# driver_board.net
KiCad netlist of a schematic drawn in EAGLE
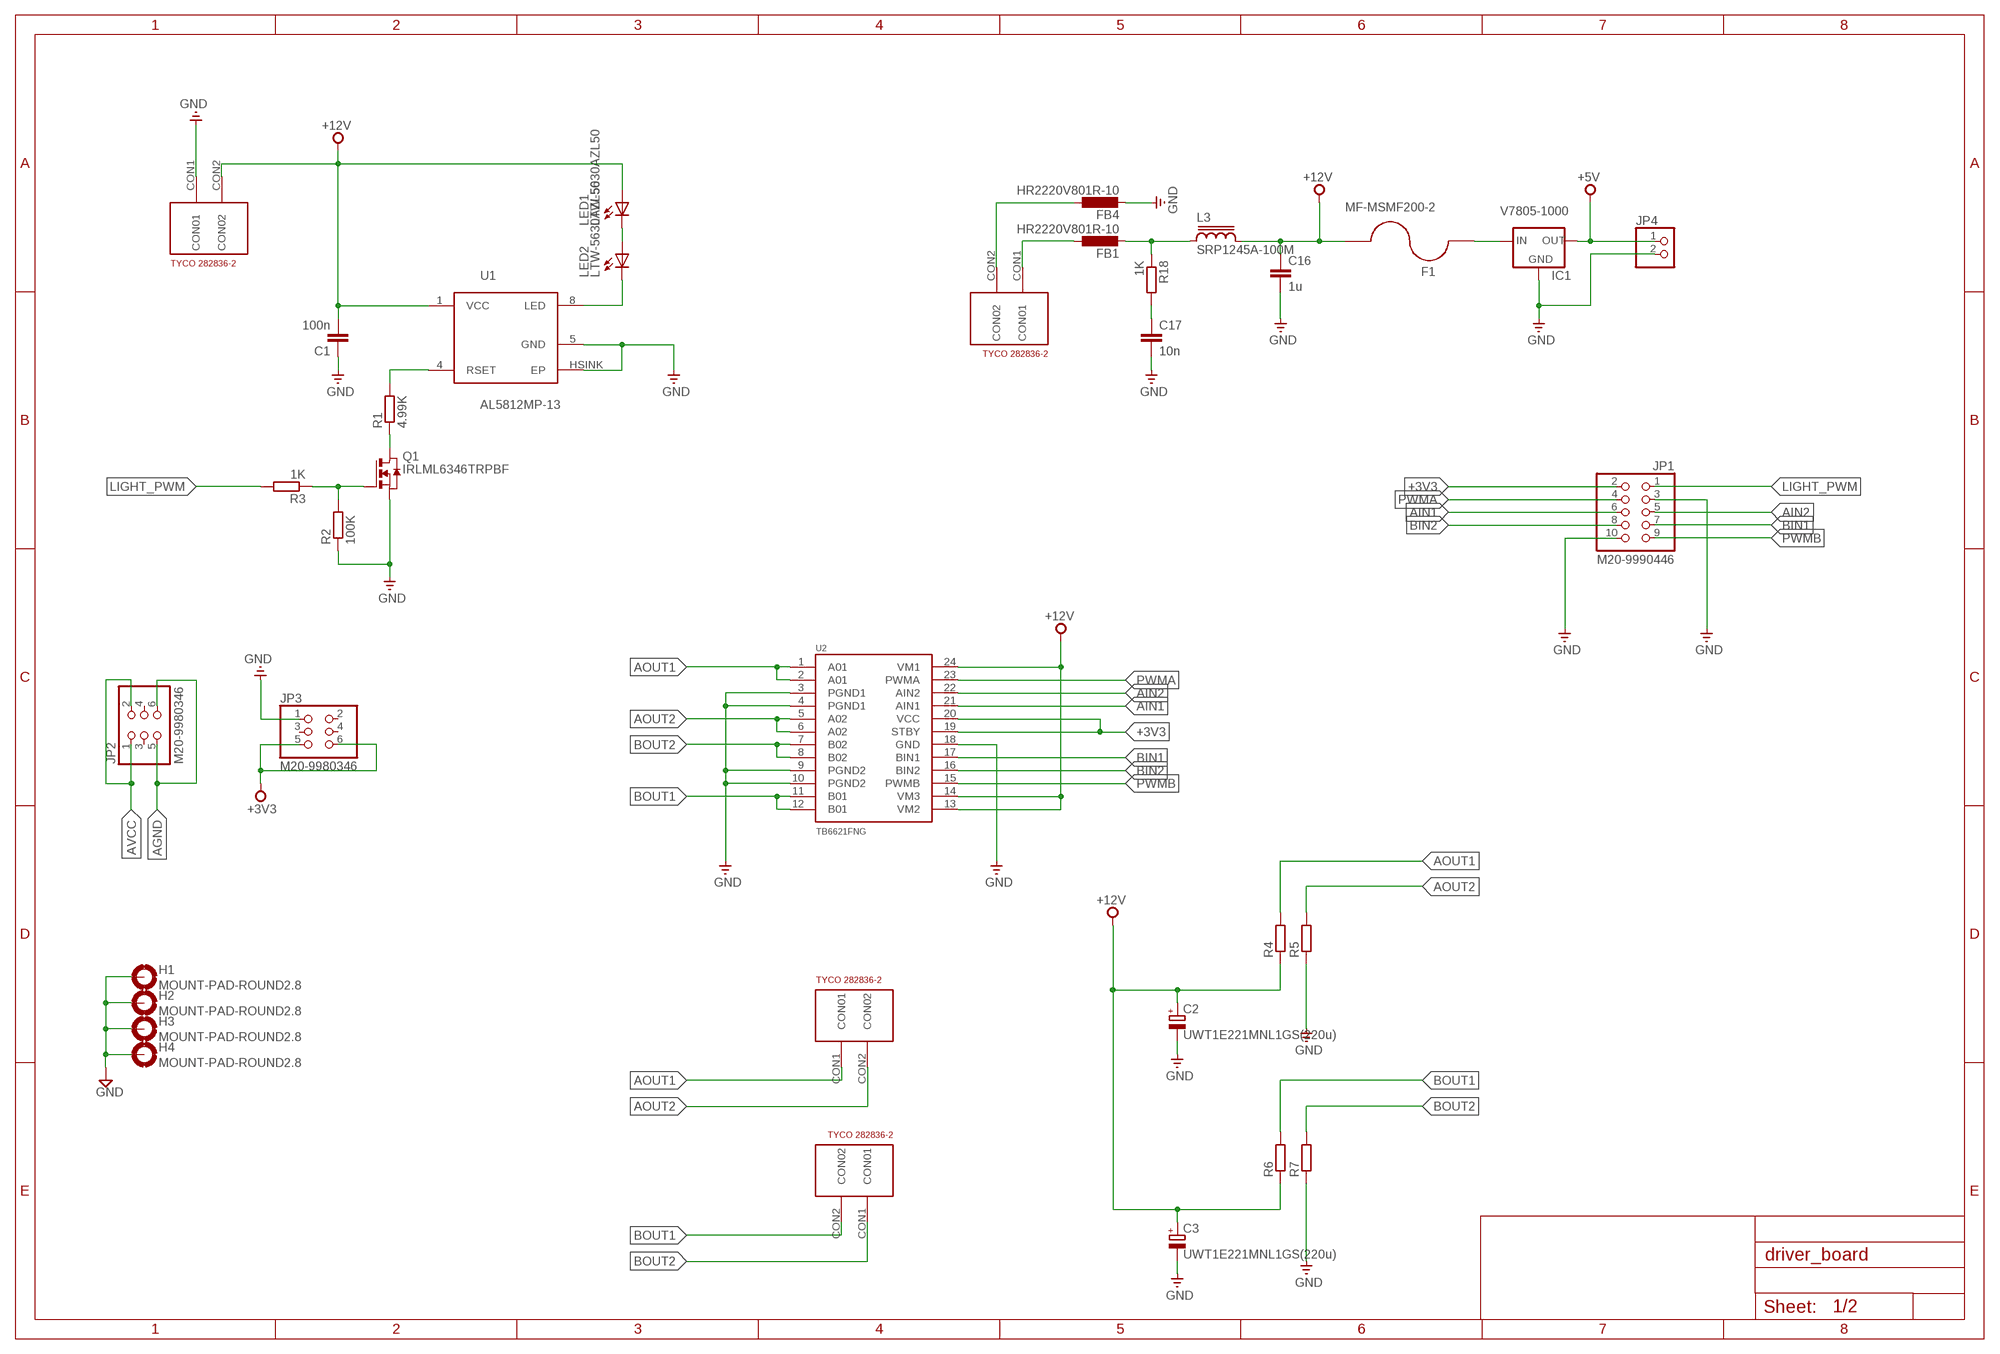
[diagram p0: schematic, sheet 1]
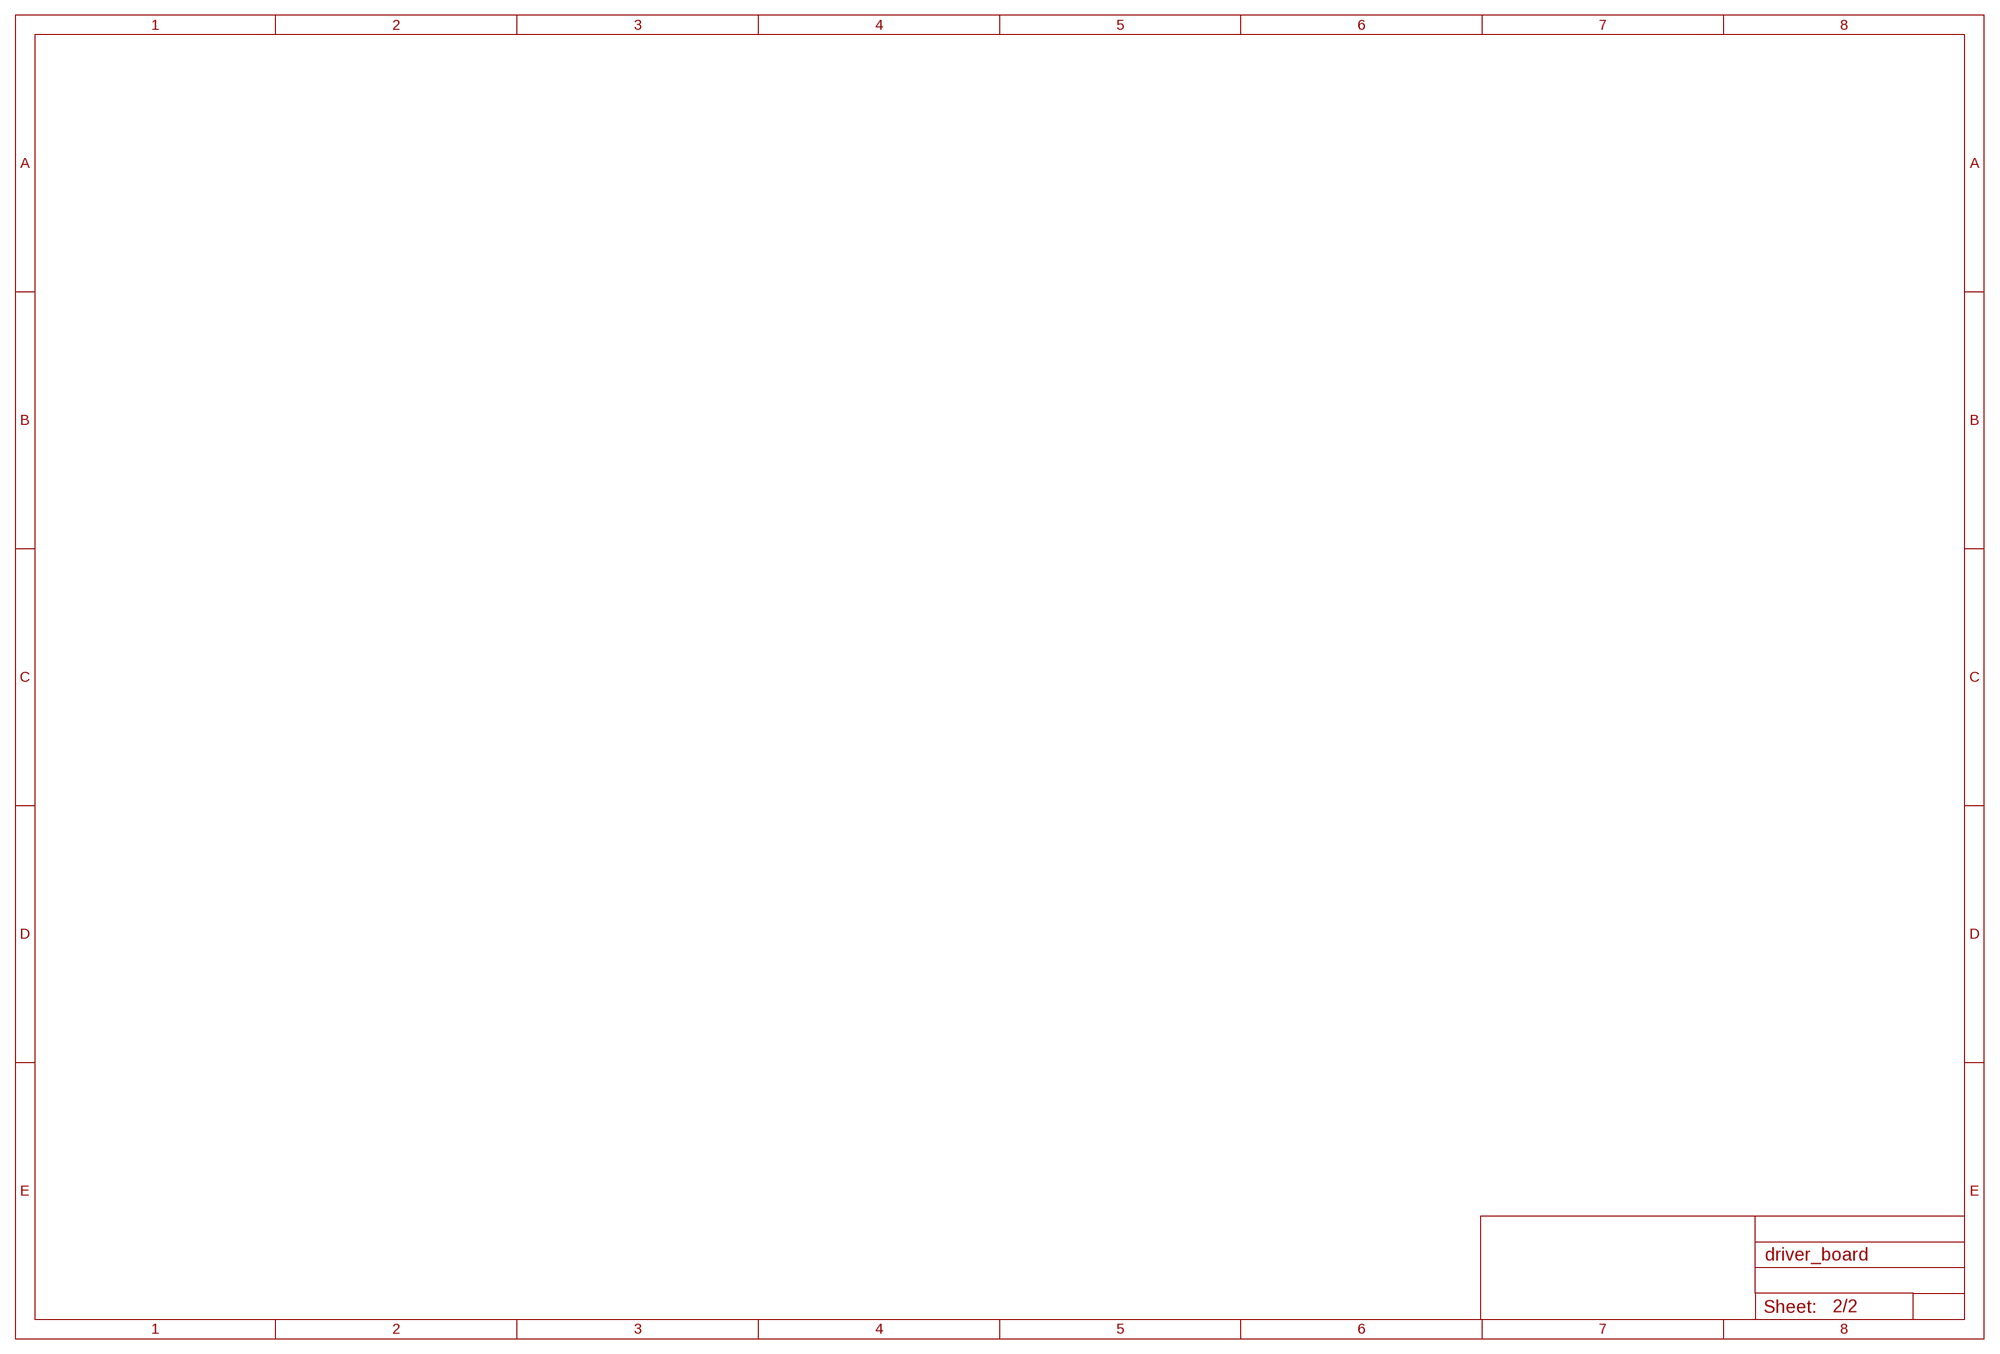
[diagram p1: schematic, sheet 2]

(export (version "E")
  (design (tool "Eeschema 10.0.6"))
  (components
    (comp (ref "C1")
      (value "100n")
      (footprint "eagle-import:C0402")
      (libsource (lib "eagle-import") (part "C-EUC0402"))
    )
    (comp (ref "C2")
      (value "UWT1E221MNL1GS(220u)")
      (footprint "eagle-import:153CLV-0810")
      (libsource (lib "eagle-import") (part "CPOL-EU153CLV-0810"))
    )
    (comp (ref "C3")
      (value "UWT1E221MNL1GS(220u)")
      (footprint "eagle-import:153CLV-0810")
      (libsource (lib "eagle-import") (part "CPOL-EU153CLV-0810"))
    )
    (comp (ref "C16")
      (value "1u")
      (footprint "eagle-import:C0402")
      (libsource (lib "eagle-import") (part "C-EUC0402"))
    )
    (comp (ref "C17")
      (value "10n")
      (footprint "eagle-import:C0402")
      (libsource (lib "eagle-import") (part "C-EUC0402"))
    )
    (comp (ref "F1")
      (value "MF-MSMF200-2")
      (footprint "eagle-import:1812")
      (fields (field (name "MANUFACTURER") "Bourns Inc.") (field (name "PART_NUMBER") "MF-MSMF075/24-2"))
      (libsource (lib "eagle-import") (part "MF-MSMF?075/24"))
    )
    (comp (ref "FB1")
      (value "HR2220V801R-10")
      (footprint "eagle-import:L5650M")
      (libsource (lib "eagle-import") (part "L-EUL5650M"))
    )
    (comp (ref "FB4")
      (value "HR2220V801R-10")
      (footprint "eagle-import:L5650M")
      (libsource (lib "eagle-import") (part "L-EUL5650M"))
    )
    (comp (ref "H1")
      (value "MOUNT-PAD-ROUND2.8")
      (footprint "eagle-import:2,8-PAD")
      (libsource (lib "eagle-import") (part "MOUNT-PAD-ROUND2.8"))
    )
    (comp (ref "H2")
      (value "MOUNT-PAD-ROUND2.8")
      (footprint "eagle-import:2,8-PAD")
      (libsource (lib "eagle-import") (part "MOUNT-PAD-ROUND2.8"))
    )
    (comp (ref "H3")
      (value "MOUNT-PAD-ROUND2.8")
      (footprint "eagle-import:2,8-PAD")
      (libsource (lib "eagle-import") (part "MOUNT-PAD-ROUND2.8"))
    )
    (comp (ref "H4")
      (value "MOUNT-PAD-ROUND2.8")
      (footprint "eagle-import:2,8-PAD")
      (libsource (lib "eagle-import") (part "MOUNT-PAD-ROUND2.8"))
    )
    (comp (ref "IC1")
      (value "V7805-1000")
      (footprint "eagle-import:DIP_3PIN")
      (libsource (lib "eagle-import") (part "VR_1OUTXX"))
    )
    (comp (ref "JP1")
      (value "M20-9990446")
      (footprint "eagle-import:2X05")
      (libsource (lib "eagle-import") (part "PINHD-2X5"))
    )
    (comp (ref "JP2")
      (value "M20-9980346")
      (footprint "eagle-import:2X03_SMT")
      (libsource (lib "eagle-import") (part "PINHD-2X3SMT"))
    )
    (comp (ref "JP3")
      (value "M20-9980346")
      (footprint "eagle-import:2X03_SMT")
      (libsource (lib "eagle-import") (part "PINHD-2X3SMT"))
    )
    (comp (ref "JP4")
      (value "PINHD-1X2")
      (footprint "eagle-import:1X02")
      (libsource (lib "eagle-import") (part "PINHD-1X2"))
    )
    (comp (ref "L3")
      (value "SRP1245A-100M")
      (footprint "eagle-import:SRP1250A")
      (libsource (lib "eagle-import") (part "SRP1250A"))
    )
    (comp (ref "LED1")
      (value "LTW-5630AZL50")
      (footprint "eagle-import:LITEON-5630")
      (libsource (lib "eagle-import") (part "LTW-5630AZL"))
    )
    (comp (ref "LED2")
      (value "LTW-5630AZL50")
      (footprint "eagle-import:LITEON-5630")
      (libsource (lib "eagle-import") (part "LTW-5630AZL"))
    )
    (comp (ref "Q1")
      (value "IRLML6346TRPBF")
      (footprint "eagle-import:SOT23")
      (libsource (lib "eagle-import") (part "NMOS-FETSOT23"))
    )
    (comp (ref "R1")
      (value "4.99K")
      (footprint "eagle-import:R0402")
      (libsource (lib "eagle-import") (part "R-EU_R0402"))
    )
    (comp (ref "R2")
      (value "100K")
      (footprint "eagle-import:R0402")
      (libsource (lib "eagle-import") (part "R-EU_R0402"))
    )
    (comp (ref "R3")
      (value "1K")
      (footprint "eagle-import:R0402")
      (libsource (lib "eagle-import") (part "R-EU_R0402"))
    )
    (comp (ref "R4")
      (value "R-EU_R0805")
      (footprint "eagle-import:R0805")
      (libsource (lib "eagle-import") (part "R-EU_R0805"))
    )
    (comp (ref "R5")
      (value "R-EU_R0805")
      (footprint "eagle-import:R0805")
      (libsource (lib "eagle-import") (part "R-EU_R0805"))
    )
    (comp (ref "R6")
      (value "R-EU_R0805")
      (footprint "eagle-import:R0805")
      (libsource (lib "eagle-import") (part "R-EU_R0805"))
    )
    (comp (ref "R7")
      (value "R-EU_R0805")
      (footprint "eagle-import:R0805")
      (libsource (lib "eagle-import") (part "R-EU_R0805"))
    )
    (comp (ref "R18")
      (value "1K")
      (footprint "eagle-import:R0402")
      (libsource (lib "eagle-import") (part "R-EU_R0402"))
    )
    (comp (ref "U$2")
      (value "282836-2")
      (footprint "eagle-import:282836-2")
      (libsource (lib "eagle-import") (part "282836-2"))
    )
    (comp (ref "U$4")
      (value "282836-2")
      (footprint "eagle-import:282836-2")
      (libsource (lib "eagle-import") (part "282836-2"))
    )
    (comp (ref "U$7")
      (value "282836-2")
      (footprint "eagle-import:282836-2")
      (libsource (lib "eagle-import") (part "282836-2"))
    )
    (comp (ref "U$8")
      (value "282836-2")
      (footprint "eagle-import:282836-2")
      (libsource (lib "eagle-import") (part "282836-2"))
    )
    (comp (ref "U1")
      (value "AL5812MP-13")
      (footprint "eagle-import:MSOP-8EP")
      (libsource (lib "eagle-import") (part "AL5812MP-13"))
    )
    (comp (ref "U2")
      (value "TB6621FNG")
      (footprint "eagle-import:SSOP24")
      (libsource (lib "eagle-import") (part "TB6621FNG"))
    )
  )
  (nets
    (net (code "1") (name "+3V3") (class "Default")
      (node (ref "JP1") (pin "2") (pinfunction "2_2") (pintype "passive"))
      (node (ref "JP3") (pin "5") (pinfunction "5_5") (pintype "passive"))
      (node (ref "JP3") (pin "6") (pinfunction "6_6") (pintype "passive"))
      (node (ref "U2") (pin "19") (pinfunction "STBY_19") (pintype "bidirectional"))
      (node (ref "U2") (pin "20") (pinfunction "VCC_20") (pintype "bidirectional"))
    )
    (net (code "2") (name "+5V") (class "Default")
      (node (ref "IC1") (pin "OUT") (pinfunction "OUT_OUT") (pintype "passive"))
      (node (ref "JP4") (pin "1") (pinfunction "1_1") (pintype "passive"))
    )
    (net (code "3") (name "+12V") (class "Default")
      (node (ref "C1") (pin "2") (pinfunction "2_2") (pintype "passive"))
      (node (ref "C16") (pin "1") (pinfunction "1_1") (pintype "passive"))
      (node (ref "C2") (pin "+") (pinfunction "+_+") (pintype "passive"))
      (node (ref "C3") (pin "+") (pinfunction "+_+") (pintype "passive"))
      (node (ref "F1") (pin "1") (pinfunction "1_1") (pintype "passive"))
      (node (ref "L3") (pin "2") (pinfunction "2_2") (pintype "passive"))
      (node (ref "LED1") (pin "A1") (pinfunction "A_A1") (pintype "passive"))
      (node (ref "LED1") (pin "A2") (pinfunction "A_A2") (pintype "passive"))
      (node (ref "LED1") (pin "A3") (pinfunction "A_A3") (pintype "passive"))
      (node (ref "R4") (pin "1") (pinfunction "1_1") (pintype "passive"))
      (node (ref "R6") (pin "1") (pinfunction "1_1") (pintype "passive"))
      (node (ref "U$4") (pin "CON2") (pinfunction "CON02_CON2") (pintype "bidirectional"))
      (node (ref "U1") (pin "1") (pinfunction "VCC_1") (pintype "bidirectional"))
      (node (ref "U2") (pin "13") (pinfunction "VM2_13") (pintype "bidirectional"))
      (node (ref "U2") (pin "14") (pinfunction "VM3_14") (pintype "bidirectional"))
      (node (ref "U2") (pin "24") (pinfunction "VM1_24") (pintype "bidirectional"))
    )
    (net (code "4") (name "AGND") (class "Default")
      (node (ref "FB4") (pin "1") (pinfunction "1_1") (pintype "passive"))
      (node (ref "JP2") (pin "5") (pinfunction "5_5") (pintype "passive"))
      (node (ref "JP2") (pin "6") (pinfunction "6_6") (pintype "passive"))
      (node (ref "U$2") (pin "CON2") (pinfunction "CON02_CON2") (pintype "bidirectional"))
    )
    (net (code "5") (name "AIN1") (class "Default")
      (node (ref "JP1") (pin "6") (pinfunction "6_6") (pintype "passive"))
      (node (ref "U2") (pin "21") (pinfunction "AIN1_21") (pintype "bidirectional"))
    )
    (net (code "6") (name "AIN2") (class "Default")
      (node (ref "JP1") (pin "5") (pinfunction "5_5") (pintype "passive"))
      (node (ref "U2") (pin "22") (pinfunction "AIN2_22") (pintype "bidirectional"))
    )
    (net (code "7") (name "AOUT1") (class "Default")
      (node (ref "R4") (pin "2") (pinfunction "2_2") (pintype "passive"))
      (node (ref "U$8") (pin "CON1") (pinfunction "CON01_CON1") (pintype "bidirectional"))
      (node (ref "U2") (pin "1") (pinfunction "A01_1") (pintype "bidirectional"))
      (node (ref "U2") (pin "2") (pinfunction "A01_2") (pintype "bidirectional"))
    )
    (net (code "8") (name "AOUT2") (class "Default")
      (node (ref "R5") (pin "2") (pinfunction "2_2") (pintype "passive"))
      (node (ref "U$8") (pin "CON2") (pinfunction "CON02_CON2") (pintype "bidirectional"))
      (node (ref "U2") (pin "5") (pinfunction "A02_5") (pintype "bidirectional"))
      (node (ref "U2") (pin "6") (pinfunction "A02_6") (pintype "bidirectional"))
    )
    (net (code "9") (name "AVCC") (class "Default")
      (node (ref "FB1") (pin "1") (pinfunction "1_1") (pintype "passive"))
      (node (ref "JP2") (pin "1") (pinfunction "1_1") (pintype "passive"))
      (node (ref "JP2") (pin "2") (pinfunction "2_2") (pintype "passive"))
      (node (ref "U$2") (pin "CON1") (pinfunction "CON01_CON1") (pintype "bidirectional"))
    )
    (net (code "10") (name "BIN1") (class "Default")
      (node (ref "JP1") (pin "7") (pinfunction "7_7") (pintype "passive"))
      (node (ref "U2") (pin "17") (pinfunction "BIN1_17") (pintype "bidirectional"))
    )
    (net (code "11") (name "BIN2") (class "Default")
      (node (ref "JP1") (pin "8") (pinfunction "8_8") (pintype "passive"))
      (node (ref "U2") (pin "16") (pinfunction "BIN2_16") (pintype "bidirectional"))
    )
    (net (code "12") (name "BOUT1") (class "Default")
      (node (ref "R6") (pin "2") (pinfunction "2_2") (pintype "passive"))
      (node (ref "U$7") (pin "CON2") (pinfunction "CON02_CON2") (pintype "bidirectional"))
      (node (ref "U2") (pin "11") (pinfunction "B01_11") (pintype "bidirectional"))
      (node (ref "U2") (pin "12") (pinfunction "B01_12") (pintype "bidirectional"))
    )
    (net (code "13") (name "BOUT2") (class "Default")
      (node (ref "R7") (pin "2") (pinfunction "2_2") (pintype "passive"))
      (node (ref "U$7") (pin "CON1") (pinfunction "CON01_CON1") (pintype "bidirectional"))
      (node (ref "U2") (pin "7") (pinfunction "B02_7") (pintype "bidirectional"))
      (node (ref "U2") (pin "8") (pinfunction "B02_8") (pintype "bidirectional"))
    )
    (net (code "14") (name "GND") (class "Default")
      (node (ref "C1") (pin "1") (pinfunction "1_1") (pintype "passive"))
      (node (ref "C16") (pin "2") (pinfunction "2_2") (pintype "passive"))
      (node (ref "C17") (pin "2") (pinfunction "2_2") (pintype "passive"))
      (node (ref "C2") (pin "-") (pinfunction "-_-") (pintype "passive"))
      (node (ref "C3") (pin "-") (pinfunction "-_-") (pintype "passive"))
      (node (ref "FB4") (pin "2") (pinfunction "2_2") (pintype "passive"))
      (node (ref "H1") (pin "B2,8") (pinfunction "MOUNT_B2,8") (pintype "passive"))
      (node (ref "H2") (pin "B2,8") (pinfunction "MOUNT_B2,8") (pintype "passive"))
      (node (ref "H3") (pin "B2,8") (pinfunction "MOUNT_B2,8") (pintype "passive"))
      (node (ref "H4") (pin "B2,8") (pinfunction "MOUNT_B2,8") (pintype "passive"))
      (node (ref "IC1") (pin "GND") (pinfunction "GND_GND") (pintype "input"))
      (node (ref "JP1") (pin "10") (pinfunction "10_10") (pintype "passive"))
      (node (ref "JP1") (pin "3") (pinfunction "3_3") (pintype "passive"))
      (node (ref "JP3") (pin "1") (pinfunction "1_1") (pintype "passive"))
      (node (ref "JP4") (pin "2") (pinfunction "2_2") (pintype "passive"))
      (node (ref "Q1") (pin "2") (pinfunction "S_2") (pintype "passive"))
      (node (ref "R2") (pin "1") (pinfunction "1_1") (pintype "passive"))
      (node (ref "R5") (pin "1") (pinfunction "1_1") (pintype "passive"))
      (node (ref "R7") (pin "1") (pinfunction "1_1") (pintype "passive"))
      (node (ref "U$4") (pin "CON1") (pinfunction "CON01_CON1") (pintype "bidirectional"))
      (node (ref "U1") (pin "5") (pinfunction "GND_5") (pintype "bidirectional"))
      (node (ref "U1") (pin "HSINK") (pinfunction "EP_HSINK") (pintype "bidirectional"))
      (node (ref "U2") (pin "10") (pinfunction "PGND2_10") (pintype "bidirectional"))
      (node (ref "U2") (pin "18") (pinfunction "GND_18") (pintype "bidirectional"))
      (node (ref "U2") (pin "3") (pinfunction "PGND1_3") (pintype "bidirectional"))
      (node (ref "U2") (pin "4") (pinfunction "PGND1_4") (pintype "bidirectional"))
      (node (ref "U2") (pin "9") (pinfunction "PGND2_9") (pintype "bidirectional"))
    )
    (net (code "15") (name "LIGHT_PWM") (class "Default")
      (node (ref "JP1") (pin "1") (pinfunction "1_1") (pintype "passive"))
      (node (ref "R3") (pin "2") (pinfunction "2_2") (pintype "passive"))
    )
    (net (code "16") (name "Net-(C17-Pad1)") (class "Default")
      (node (ref "C17") (pin "1") (pinfunction "1_1") (pintype "passive"))
      (node (ref "R18") (pin "2") (pinfunction "2_2") (pintype "passive"))
    )
    (net (code "17") (name "Net-(F1-Pad2)") (class "Default")
      (node (ref "F1") (pin "2") (pinfunction "2_2") (pintype "passive"))
      (node (ref "IC1") (pin "IN") (pinfunction "IN_IN") (pintype "input"))
    )
    (net (code "18") (name "Net-(FB1-Pad2)") (class "Default")
      (node (ref "FB1") (pin "2") (pinfunction "2_2") (pintype "passive"))
      (node (ref "L3") (pin "1") (pinfunction "1_1") (pintype "passive"))
      (node (ref "R18") (pin "1") (pinfunction "1_1") (pintype "passive"))
    )
    (net (code "19") (name "Net-(LED1-C-PadC1)") (class "Default")
      (node (ref "LED1") (pin "C1") (pinfunction "C_C1") (pintype "passive"))
      (node (ref "LED1") (pin "C2") (pinfunction "C_C2") (pintype "passive"))
      (node (ref "LED2") (pin "A1") (pinfunction "A_A1") (pintype "passive"))
      (node (ref "LED2") (pin "A2") (pinfunction "A_A2") (pintype "passive"))
      (node (ref "LED2") (pin "A3") (pinfunction "A_A3") (pintype "passive"))
    )
    (net (code "20") (name "Net-(Q1-D)") (class "Default")
      (node (ref "Q1") (pin "3") (pinfunction "D_3") (pintype "passive"))
      (node (ref "R1") (pin "1") (pinfunction "1_1") (pintype "passive"))
    )
    (net (code "21") (name "Net-(Q1-G)") (class "Default")
      (node (ref "Q1") (pin "1") (pinfunction "G_1") (pintype "passive"))
      (node (ref "R2") (pin "2") (pinfunction "2_2") (pintype "passive"))
      (node (ref "R3") (pin "1") (pinfunction "1_1") (pintype "passive"))
    )
    (net (code "22") (name "Net-(U1-LED)") (class "Default")
      (node (ref "LED2") (pin "C1") (pinfunction "C_C1") (pintype "passive"))
      (node (ref "LED2") (pin "C2") (pinfunction "C_C2") (pintype "passive"))
      (node (ref "U1") (pin "8") (pinfunction "LED_8") (pintype "bidirectional"))
    )
    (net (code "23") (name "Net-(U1-RSET)") (class "Default")
      (node (ref "R1") (pin "2") (pinfunction "2_2") (pintype "passive"))
      (node (ref "U1") (pin "4") (pinfunction "RSET_4") (pintype "bidirectional"))
    )
    (net (code "24") (name "PWMA") (class "Default")
      (node (ref "JP1") (pin "4") (pinfunction "4_4") (pintype "passive"))
      (node (ref "U2") (pin "23") (pinfunction "PWMA_23") (pintype "bidirectional"))
    )
    (net (code "25") (name "PWMB") (class "Default")
      (node (ref "JP1") (pin "9") (pinfunction "9_9") (pintype "passive"))
      (node (ref "U2") (pin "15") (pinfunction "PWMB_15") (pintype "bidirectional"))
    )
    (net (code "26") (name "unconnected-(JP2-Pad3)") (class "Default")
      (node (ref "JP2") (pin "3") (pinfunction "3_3") (pintype "passive"))
    )
    (net (code "27") (name "unconnected-(JP2-Pad4)") (class "Default")
      (node (ref "JP2") (pin "4") (pinfunction "4_4") (pintype "passive"))
    )
    (net (code "28") (name "unconnected-(JP3-Pad2)") (class "Default")
      (node (ref "JP3") (pin "2") (pinfunction "2_2") (pintype "passive"))
    )
    (net (code "29") (name "unconnected-(JP3-Pad3)") (class "Default")
      (node (ref "JP3") (pin "3") (pinfunction "3_3") (pintype "passive"))
    )
    (net (code "30") (name "unconnected-(JP3-Pad4)") (class "Default")
      (node (ref "JP3") (pin "4") (pinfunction "4_4") (pintype "passive"))
    )
  )
)
